# 07_-_UNUSED.net
KiCad netlist of a schematic drawn in Altium Designer
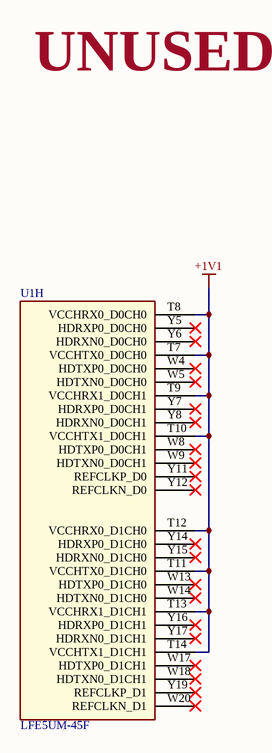
[diagram p0: [07] - UNUSED.SchDoc]

(export (version "E")
  (design (tool "Eeschema 10.0.6"))
  (components
    (comp (ref "U1")
      (value "LFE5UM-45F")
      (footprint "LFE5BG381")
      (description "ECP5 Series 44 K LUTs 203 I/O 1.1 V Slow Surface Mount FPGA - CABGA-381")
      (fields
        (field (name "MANUFACTURER") "Lattice Semiconductor")
        (field (name "MANUFACTURER PART NUMBER") "LFE5UM-45F-6BG381C")
      )
      (libsource (lib "ECP5_V2") (part "LFE5UM-45F-6BG381C"))
    )
  )
  (nets
    (net (code "1") (name "+1V1") (class "Default")
      (node (ref "U1") (pin "T10") (pinfunction "VCCHTX1_D0CH1_T10") (pintype "power_in"))
      (node (ref "U1") (pin "T11") (pinfunction "VCCHTX0_D1CH0_T11") (pintype "power_in"))
      (node (ref "U1") (pin "T12") (pinfunction "VCCHRX0_D1CH0_T12") (pintype "power_in"))
      (node (ref "U1") (pin "T13") (pinfunction "VCCHRX1_D1CH1_T13") (pintype "power_in"))
      (node (ref "U1") (pin "T14") (pinfunction "VCCHTX1_D1CH1_T14") (pintype "power_in"))
      (node (ref "U1") (pin "T7") (pinfunction "VCCHTX0_D0CH0_T7") (pintype "power_in"))
      (node (ref "U1") (pin "T8") (pinfunction "VCCHRX0_D0CH0_T8") (pintype "power_in"))
      (node (ref "U1") (pin "T9") (pinfunction "VCCHRX1_D0CH1_T9") (pintype "power_in"))
    )
    (net (code "2") (name "unconnected-(U1H-HDRXN0_D0CH0-PadY6)") (class "Default")
      (node (ref "U1") (pin "Y6") (pinfunction "HDRXN0_D0CH0_Y6") (pintype "power_in+no_connect"))
    )
    (net (code "3") (name "unconnected-(U1H-HDRXN0_D0CH1-PadY8)") (class "Default")
      (node (ref "U1") (pin "Y8") (pinfunction "HDRXN0_D0CH1_Y8") (pintype "power_in+no_connect"))
    )
    (net (code "4") (name "unconnected-(U1H-HDRXN0_D1CH0-PadY15)") (class "Default")
      (node (ref "U1") (pin "Y15") (pinfunction "HDRXN0_D1CH0_Y15") (pintype "power_in+no_connect"))
    )
    (net (code "5") (name "unconnected-(U1H-HDRXN0_D1CH1-PadY17)") (class "Default")
      (node (ref "U1") (pin "Y17") (pinfunction "HDRXN0_D1CH1_Y17") (pintype "power_in+no_connect"))
    )
    (net (code "6") (name "unconnected-(U1H-HDRXP0_D0CH0-PadY5)") (class "Default")
      (node (ref "U1") (pin "Y5") (pinfunction "HDRXP0_D0CH0_Y5") (pintype "power_in+no_connect"))
    )
    (net (code "7") (name "unconnected-(U1H-HDRXP0_D0CH1-PadY7)") (class "Default")
      (node (ref "U1") (pin "Y7") (pinfunction "HDRXP0_D0CH1_Y7") (pintype "power_in+no_connect"))
    )
    (net (code "8") (name "unconnected-(U1H-HDRXP0_D1CH0-PadY14)") (class "Default")
      (node (ref "U1") (pin "Y14") (pinfunction "HDRXP0_D1CH0_Y14") (pintype "power_in+no_connect"))
    )
    (net (code "9") (name "unconnected-(U1H-HDRXP0_D1CH1-PadY16)") (class "Default")
      (node (ref "U1") (pin "Y16") (pinfunction "HDRXP0_D1CH1_Y16") (pintype "power_in+no_connect"))
    )
    (net (code "10") (name "unconnected-(U1H-HDTXN0_D0CH0-PadW5)") (class "Default")
      (node (ref "U1") (pin "W5") (pinfunction "HDTXN0_D0CH0_W5") (pintype "power_in+no_connect"))
    )
    (net (code "11") (name "unconnected-(U1H-HDTXN0_D0CH1-PadW9)") (class "Default")
      (node (ref "U1") (pin "W9") (pinfunction "HDTXN0_D0CH1_W9") (pintype "power_in+no_connect"))
    )
    (net (code "12") (name "unconnected-(U1H-HDTXN0_D1CH0-PadW14)") (class "Default")
      (node (ref "U1") (pin "W14") (pinfunction "HDTXN0_D1CH0_W14") (pintype "power_in+no_connect"))
    )
    (net (code "13") (name "unconnected-(U1H-HDTXN0_D1CH1-PadW18)") (class "Default")
      (node (ref "U1") (pin "W18") (pinfunction "HDTXN0_D1CH1_W18") (pintype "power_in+no_connect"))
    )
    (net (code "14") (name "unconnected-(U1H-HDTXP0_D0CH0-PadW4)") (class "Default")
      (node (ref "U1") (pin "W4") (pinfunction "HDTXP0_D0CH0_W4") (pintype "passive+no_connect"))
    )
    (net (code "15") (name "unconnected-(U1H-HDTXP0_D0CH1-PadW8)") (class "Default")
      (node (ref "U1") (pin "W8") (pinfunction "HDTXP0_D0CH1_W8") (pintype "power_in+no_connect"))
    )
    (net (code "16") (name "unconnected-(U1H-HDTXP0_D1CH0-PadW13)") (class "Default")
      (node (ref "U1") (pin "W13") (pinfunction "HDTXP0_D1CH0_W13") (pintype "power_in+no_connect"))
    )
    (net (code "17") (name "unconnected-(U1H-HDTXP0_D1CH1-PadW17)") (class "Default")
      (node (ref "U1") (pin "W17") (pinfunction "HDTXP0_D1CH1_W17") (pintype "power_in+no_connect"))
    )
    (net (code "18") (name "unconnected-(U1H-REFCLKN_D0-PadY12)") (class "Default")
      (node (ref "U1") (pin "Y12") (pinfunction "REFCLKN_D0_Y12") (pintype "power_in+no_connect"))
    )
    (net (code "19") (name "unconnected-(U1H-REFCLKN_D1-PadW20)") (class "Default")
      (node (ref "U1") (pin "W20") (pinfunction "REFCLKN_D1_W20") (pintype "power_in+no_connect"))
    )
    (net (code "20") (name "unconnected-(U1H-REFCLKP_D0-PadY11)") (class "Default")
      (node (ref "U1") (pin "Y11") (pinfunction "REFCLKP_D0_Y11") (pintype "power_in+no_connect"))
    )
    (net (code "21") (name "unconnected-(U1H-REFCLKP_D1-PadY19)") (class "Default")
      (node (ref "U1") (pin "Y19") (pinfunction "REFCLKP_D1_Y19") (pintype "power_in+no_connect"))
    )
  )
)
